# FPGA_Supply.net
KiCad netlist of a schematic drawn in Altium Designer
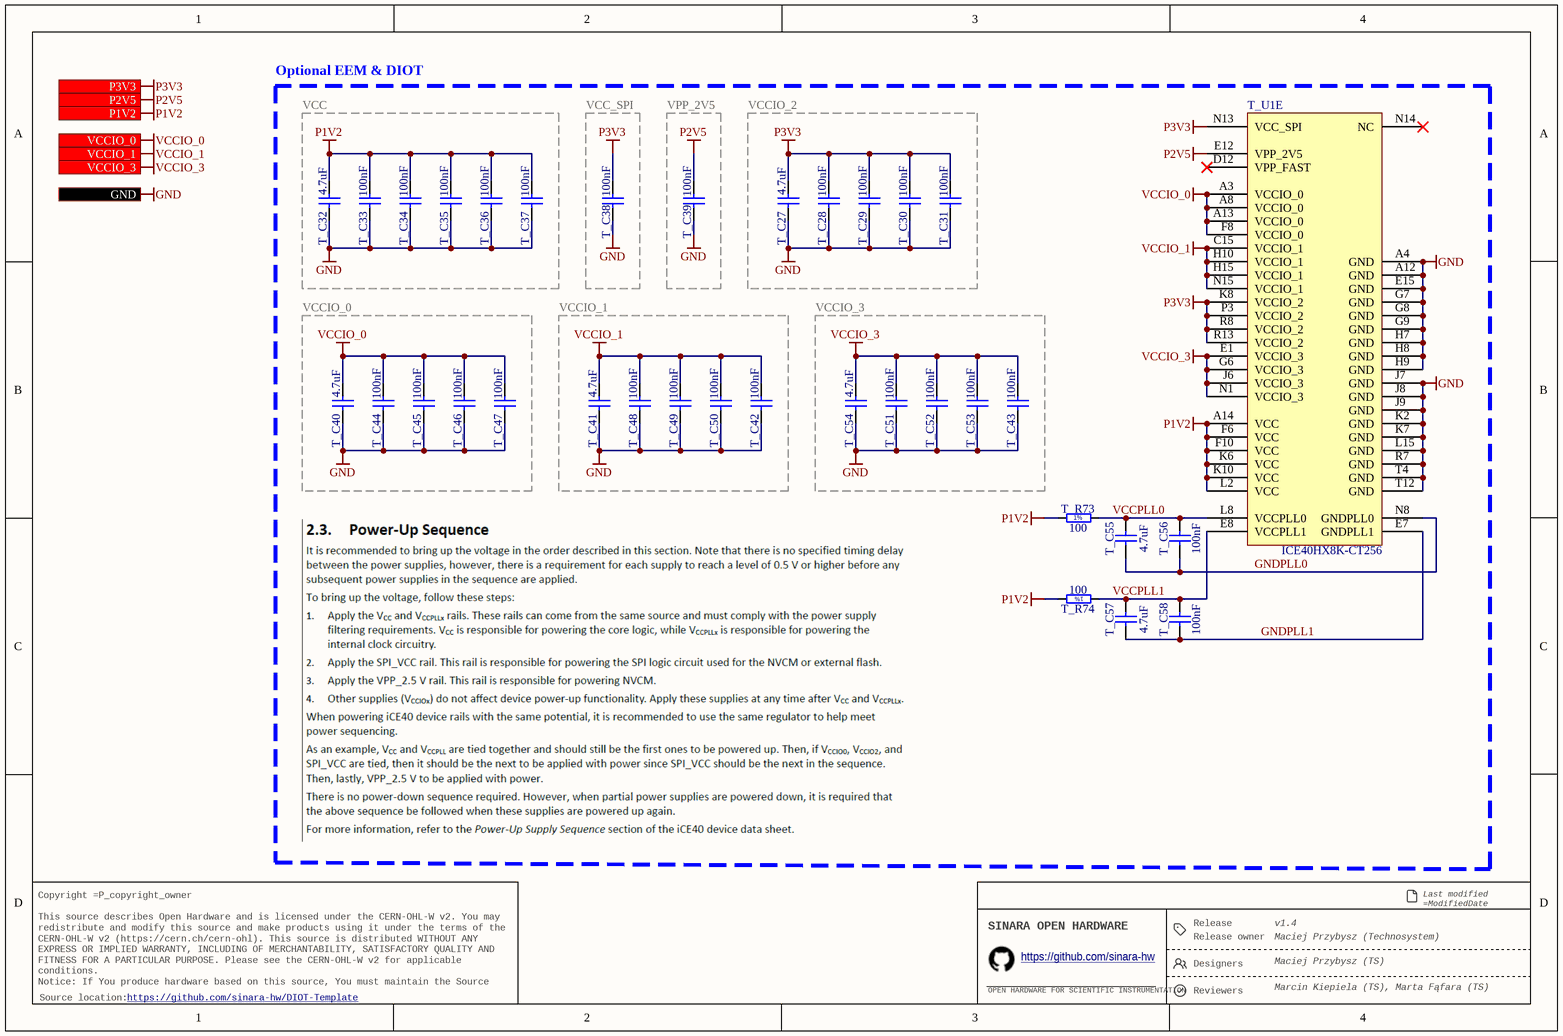
[diagram p0: FPGA_Supply.SchDoc]

(export (version "E")
  (design (tool "Eeschema 10.0.6"))
  (components
    (comp (ref "T_C27")
      (value "4.7uF")
      (footprint "CAPC2012X135N")
      (description "Non-polarised capacitor")
      (fields
        (field (name "PART NUMBER") "CC0805_4.7UF_16V_10%_X7R")
        (field (name "VOLTAGE") "16V")
        (field (name "AUTHOR") "CERN DEM JLC")
      )
      (libsource (lib "Capacitors") (part "Capacitor - non polarized"))
    )
    (comp (ref "T_C28")
      (value "100nF")
      (footprint "CAPC1005X55N")
      (description "Non-polarised capacitor")
      (fields
        (field (name "PART NUMBER") "CC0402_100NF_50V_10%_X7R")
        (field (name "VOLTAGE") "50V")
        (field (name "AUTHOR") "CERN DEM MR")
      )
      (libsource (lib "Capacitors") (part "Capacitor - non polarized"))
    )
    (comp (ref "T_C29")
      (value "100nF")
      (footprint "CAPC1005X55N")
      (description "Non-polarised capacitor")
      (fields
        (field (name "PART NUMBER") "CC0402_100NF_50V_10%_X7R")
        (field (name "VOLTAGE") "50V")
        (field (name "AUTHOR") "CERN DEM MR")
      )
      (libsource (lib "Capacitors") (part "Capacitor - non polarized"))
    )
    (comp (ref "T_C30")
      (value "100nF")
      (footprint "CAPC1005X55N")
      (description "Non-polarised capacitor")
      (fields
        (field (name "PART NUMBER") "CC0402_100NF_50V_10%_X7R")
        (field (name "VOLTAGE") "50V")
        (field (name "AUTHOR") "CERN DEM MR")
      )
      (libsource (lib "Capacitors") (part "Capacitor - non polarized"))
    )
    (comp (ref "T_C31")
      (value "100nF")
      (footprint "CAPC1005X55N")
      (description "Non-polarised capacitor")
      (fields
        (field (name "PART NUMBER") "CC0402_100NF_50V_10%_X7R")
        (field (name "VOLTAGE") "50V")
        (field (name "AUTHOR") "CERN DEM MR")
      )
      (libsource (lib "Capacitors") (part "Capacitor - non polarized"))
    )
    (comp (ref "T_C32")
      (value "4.7uF")
      (footprint "CAPC2012X135N")
      (description "Non-polarised capacitor")
      (fields
        (field (name "PART NUMBER") "CC0805_4.7UF_16V_10%_X7R")
        (field (name "VOLTAGE") "16V")
        (field (name "AUTHOR") "CERN DEM JLC")
      )
      (libsource (lib "Capacitors") (part "Capacitor - non polarized"))
    )
    (comp (ref "T_C33")
      (value "100nF")
      (footprint "CAPC1005X55N")
      (description "Non-polarised capacitor")
      (fields
        (field (name "PART NUMBER") "CC0402_100NF_50V_10%_X7R")
        (field (name "VOLTAGE") "50V")
        (field (name "AUTHOR") "CERN DEM MR")
      )
      (libsource (lib "Capacitors") (part "Capacitor - non polarized"))
    )
    (comp (ref "T_C34")
      (value "100nF")
      (footprint "CAPC1005X55N")
      (description "Non-polarised capacitor")
      (fields
        (field (name "PART NUMBER") "CC0402_100NF_50V_10%_X7R")
        (field (name "VOLTAGE") "50V")
        (field (name "AUTHOR") "CERN DEM MR")
      )
      (libsource (lib "Capacitors") (part "Capacitor - non polarized"))
    )
    (comp (ref "T_C35")
      (value "100nF")
      (footprint "CAPC1005X55N")
      (description "Non-polarised capacitor")
      (fields
        (field (name "PART NUMBER") "CC0402_100NF_50V_10%_X7R")
        (field (name "VOLTAGE") "50V")
        (field (name "AUTHOR") "CERN DEM MR")
      )
      (libsource (lib "Capacitors") (part "Capacitor - non polarized"))
    )
    (comp (ref "T_C36")
      (value "100nF")
      (footprint "CAPC1005X55N")
      (description "Non-polarised capacitor")
      (fields
        (field (name "PART NUMBER") "CC0402_100NF_50V_10%_X7R")
        (field (name "VOLTAGE") "50V")
        (field (name "AUTHOR") "CERN DEM MR")
      )
      (libsource (lib "Capacitors") (part "Capacitor - non polarized"))
    )
    (comp (ref "T_C37")
      (value "100nF")
      (footprint "CAPC1005X55N")
      (description "Non-polarised capacitor")
      (fields
        (field (name "PART NUMBER") "CC0402_100NF_50V_10%_X7R")
        (field (name "VOLTAGE") "50V")
        (field (name "AUTHOR") "CERN DEM MR")
      )
      (libsource (lib "Capacitors") (part "Capacitor - non polarized"))
    )
    (comp (ref "T_C38")
      (value "100nF")
      (footprint "CAPC1005X55N")
      (description "Non-polarised capacitor")
      (fields
        (field (name "PART NUMBER") "CC0402_100NF_50V_10%_X7R")
        (field (name "VOLTAGE") "50V")
        (field (name "AUTHOR") "CERN DEM MR")
      )
      (libsource (lib "Capacitors") (part "Capacitor - non polarized"))
    )
    (comp (ref "T_C39")
      (value "100nF")
      (footprint "CAPC1005X55N")
      (description "Non-polarised capacitor")
      (fields
        (field (name "PART NUMBER") "CC0402_100NF_50V_10%_X7R")
        (field (name "VOLTAGE") "50V")
        (field (name "AUTHOR") "CERN DEM MR")
      )
      (libsource (lib "Capacitors") (part "Capacitor - non polarized"))
    )
    (comp (ref "T_C40")
      (value "4.7uF")
      (footprint "CAPC2012X135N")
      (description "Non-polarised capacitor")
      (fields
        (field (name "PART NUMBER") "CC0805_4.7UF_16V_10%_X7R")
        (field (name "VOLTAGE") "16V")
        (field (name "AUTHOR") "CERN DEM JLC")
      )
      (libsource (lib "Capacitors") (part "Capacitor - non polarized"))
    )
    (comp (ref "T_C41")
      (value "4.7uF")
      (footprint "CAPC2012X135N")
      (description "Non-polarised capacitor")
      (fields
        (field (name "PART NUMBER") "CC0805_4.7UF_16V_10%_X7R")
        (field (name "VOLTAGE") "16V")
        (field (name "AUTHOR") "CERN DEM JLC")
      )
      (libsource (lib "Capacitors") (part "Capacitor - non polarized"))
    )
    (comp (ref "T_C42")
      (value "100nF")
      (footprint "CAPC1005X55N")
      (description "Non-polarised capacitor")
      (fields
        (field (name "PART NUMBER") "CC0402_100NF_50V_10%_X7R")
        (field (name "VOLTAGE") "50V")
        (field (name "AUTHOR") "CERN DEM MR")
      )
      (libsource (lib "Capacitors") (part "Capacitor - non polarized"))
    )
    (comp (ref "T_C43")
      (value "100nF")
      (footprint "CAPC1005X55N")
      (description "Non-polarised capacitor")
      (fields
        (field (name "PART NUMBER") "CC0402_100NF_50V_10%_X7R")
        (field (name "VOLTAGE") "50V")
        (field (name "AUTHOR") "CERN DEM MR")
      )
      (libsource (lib "Capacitors") (part "Capacitor - non polarized"))
    )
    (comp (ref "T_C44")
      (value "100nF")
      (footprint "CAPC1005X55N")
      (description "Non-polarised capacitor")
      (fields
        (field (name "PART NUMBER") "CC0402_100NF_50V_10%_X7R")
        (field (name "VOLTAGE") "50V")
        (field (name "AUTHOR") "CERN DEM MR")
      )
      (libsource (lib "Capacitors") (part "Capacitor - non polarized"))
    )
    (comp (ref "T_C45")
      (value "100nF")
      (footprint "CAPC1005X55N")
      (description "Non-polarised capacitor")
      (fields
        (field (name "PART NUMBER") "CC0402_100NF_50V_10%_X7R")
        (field (name "VOLTAGE") "50V")
        (field (name "AUTHOR") "CERN DEM MR")
      )
      (libsource (lib "Capacitors") (part "Capacitor - non polarized"))
    )
    (comp (ref "T_C46")
      (value "100nF")
      (footprint "CAPC1005X55N")
      (description "Non-polarised capacitor")
      (fields
        (field (name "PART NUMBER") "CC0402_100NF_50V_10%_X7R")
        (field (name "VOLTAGE") "50V")
        (field (name "AUTHOR") "CERN DEM MR")
      )
      (libsource (lib "Capacitors") (part "Capacitor - non polarized"))
    )
    (comp (ref "T_C47")
      (value "100nF")
      (footprint "CAPC1005X55N")
      (description "Non-polarised capacitor")
      (fields
        (field (name "PART NUMBER") "CC0402_100NF_50V_10%_X7R")
        (field (name "VOLTAGE") "50V")
        (field (name "AUTHOR") "CERN DEM MR")
      )
      (libsource (lib "Capacitors") (part "Capacitor - non polarized"))
    )
    (comp (ref "T_C48")
      (value "100nF")
      (footprint "CAPC1005X55N")
      (description "Non-polarised capacitor")
      (fields
        (field (name "PART NUMBER") "CC0402_100NF_50V_10%_X7R")
        (field (name "VOLTAGE") "50V")
        (field (name "AUTHOR") "CERN DEM MR")
      )
      (libsource (lib "Capacitors") (part "Capacitor - non polarized"))
    )
    (comp (ref "T_C49")
      (value "100nF")
      (footprint "CAPC1005X55N")
      (description "Non-polarised capacitor")
      (fields
        (field (name "PART NUMBER") "CC0402_100NF_50V_10%_X7R")
        (field (name "VOLTAGE") "50V")
        (field (name "AUTHOR") "CERN DEM MR")
      )
      (libsource (lib "Capacitors") (part "Capacitor - non polarized"))
    )
    (comp (ref "T_C50")
      (value "100nF")
      (footprint "CAPC1005X55N")
      (description "Non-polarised capacitor")
      (fields
        (field (name "PART NUMBER") "CC0402_100NF_50V_10%_X7R")
        (field (name "VOLTAGE") "50V")
        (field (name "AUTHOR") "CERN DEM MR")
      )
      (libsource (lib "Capacitors") (part "Capacitor - non polarized"))
    )
    (comp (ref "T_C51")
      (value "100nF")
      (footprint "CAPC1005X55N")
      (description "Non-polarised capacitor")
      (fields
        (field (name "PART NUMBER") "CC0402_100NF_50V_10%_X7R")
        (field (name "VOLTAGE") "50V")
        (field (name "AUTHOR") "CERN DEM MR")
      )
      (libsource (lib "Capacitors") (part "Capacitor - non polarized"))
    )
    (comp (ref "T_C52")
      (value "100nF")
      (footprint "CAPC1005X55N")
      (description "Non-polarised capacitor")
      (fields
        (field (name "PART NUMBER") "CC0402_100NF_50V_10%_X7R")
        (field (name "VOLTAGE") "50V")
        (field (name "AUTHOR") "CERN DEM MR")
      )
      (libsource (lib "Capacitors") (part "Capacitor - non polarized"))
    )
    (comp (ref "T_C53")
      (value "100nF")
      (footprint "CAPC1005X55N")
      (description "Non-polarised capacitor")
      (fields
        (field (name "PART NUMBER") "CC0402_100NF_50V_10%_X7R")
        (field (name "VOLTAGE") "50V")
        (field (name "AUTHOR") "CERN DEM MR")
      )
      (libsource (lib "Capacitors") (part "Capacitor - non polarized"))
    )
    (comp (ref "T_C54")
      (value "4.7uF")
      (footprint "CAPC2012X135N")
      (description "Non-polarised capacitor")
      (fields
        (field (name "PART NUMBER") "CC0805_4.7UF_16V_10%_X7R")
        (field (name "VOLTAGE") "16V")
        (field (name "AUTHOR") "CERN DEM JLC")
      )
      (libsource (lib "Capacitors") (part "Capacitor - non polarized"))
    )
    (comp (ref "T_C55")
      (value "4.7uF")
      (footprint "CAPC2012X135N")
      (description "Non-polarised capacitor")
      (fields
        (field (name "PART NUMBER") "CC0805_4.7UF_16V_10%_X7R")
        (field (name "VOLTAGE") "16V")
        (field (name "AUTHOR") "CERN DEM JLC")
      )
      (libsource (lib "Capacitors") (part "Capacitor - non polarized"))
    )
    (comp (ref "T_C56")
      (value "100nF")
      (footprint "CAPC1005X55N")
      (description "Non-polarised capacitor")
      (fields
        (field (name "PART NUMBER") "CC0402_100NF_50V_10%_X7R")
        (field (name "VOLTAGE") "50V")
        (field (name "AUTHOR") "CERN DEM MR")
      )
      (libsource (lib "Capacitors") (part "Capacitor - non polarized"))
    )
    (comp (ref "T_C57")
      (value "4.7uF")
      (footprint "CAPC2012X135N")
      (description "Non-polarised capacitor")
      (fields
        (field (name "PART NUMBER") "CC0805_4.7UF_16V_10%_X7R")
        (field (name "VOLTAGE") "16V")
        (field (name "AUTHOR") "CERN DEM JLC")
      )
      (libsource (lib "Capacitors") (part "Capacitor - non polarized"))
    )
    (comp (ref "T_C58")
      (value "100nF")
      (footprint "CAPC1005X55N")
      (description "Non-polarised capacitor")
      (fields
        (field (name "PART NUMBER") "CC0402_100NF_50V_10%_X7R")
        (field (name "VOLTAGE") "50V")
        (field (name "AUTHOR") "CERN DEM MR")
      )
      (libsource (lib "Capacitors") (part "Capacitor - non polarized"))
    )
    (comp (ref "T_R73")
      (value "100")
      (footprint "RESC1005X40N")
      (description "Resistor - 1%")
      (fields
        (field (name "PART NUMBER") "R0402_100R_1%_0.0625W_100PPM")
        (field (name "POWER") "0.0625W")
        (field (name "AUTHOR") "CERN DEM JLC")
      )
      (libsource (lib "Resistors") (part "Resistor - 1%"))
    )
    (comp (ref "T_R74")
      (value "100")
      (footprint "RESC1005X40N")
      (description "Resistor - 1%")
      (fields
        (field (name "PART NUMBER") "R0402_100R_1%_0.0625W_100PPM")
        (field (name "POWER") "0.0625W")
        (field (name "AUTHOR") "CERN DEM JLC")
      )
      (libsource (lib "Resistors") (part "Resistor - 1%"))
    )
    (comp (ref "T_U1")
      (value "ICE40HX8K-CT256")
      (footprint "LATC-caBGA-256")
      (fields (field (name "MANUFACTURER") "Lattice Semiconductor"))
      (libsource (lib "Altium Content Vault") (part "LATC-HX8K-caBGA-256"))
    )
  )
  (nets
    (net (code "1") (name "/GNDPLL0") (class "Default")
      (node (ref "T_C55") (pin "1") (pinfunction "1_1") (pintype "passive"))
      (node (ref "T_C56") (pin "1") (pinfunction "1_1") (pintype "passive"))
      (node (ref "T_U1") (pin "N8") (pinfunction "GNDPLL0_N8") (pintype "power_in"))
    )
    (net (code "2") (name "/GNDPLL1") (class "Default")
      (node (ref "T_C57") (pin "1") (pinfunction "1_1") (pintype "passive"))
      (node (ref "T_C58") (pin "1") (pinfunction "1_1") (pintype "passive"))
      (node (ref "T_U1") (pin "E7") (pinfunction "GNDPLL1_E7") (pintype "power_in"))
    )
    (net (code "3") (name "/VCCPLL0") (class "Default")
      (node (ref "T_C55") (pin "2") (pinfunction "2_2") (pintype "passive"))
      (node (ref "T_C56") (pin "2") (pinfunction "2_2") (pintype "passive"))
      (node (ref "T_R73") (pin "2") (pinfunction "2_2") (pintype "passive"))
      (node (ref "T_U1") (pin "L8") (pinfunction "VCCPLL0_L8") (pintype "power_in"))
    )
    (net (code "4") (name "/VCCPLL1") (class "Default")
      (node (ref "T_C57") (pin "2") (pinfunction "2_2") (pintype "passive"))
      (node (ref "T_C58") (pin "2") (pinfunction "2_2") (pintype "passive"))
      (node (ref "T_R74") (pin "1") (pinfunction "1_1") (pintype "passive"))
      (node (ref "T_U1") (pin "E8") (pinfunction "VCCPLL1_E8") (pintype "power_in"))
    )
    (net (code "5") (name "GND") (class "Default")
      (node (ref "T_C27") (pin "1") (pinfunction "1_1") (pintype "passive"))
      (node (ref "T_C28") (pin "1") (pinfunction "1_1") (pintype "passive"))
      (node (ref "T_C29") (pin "1") (pinfunction "1_1") (pintype "passive"))
      (node (ref "T_C30") (pin "1") (pinfunction "1_1") (pintype "passive"))
      (node (ref "T_C31") (pin "1") (pinfunction "1_1") (pintype "passive"))
      (node (ref "T_C32") (pin "1") (pinfunction "1_1") (pintype "passive"))
      (node (ref "T_C33") (pin "1") (pinfunction "1_1") (pintype "passive"))
      (node (ref "T_C34") (pin "1") (pinfunction "1_1") (pintype "passive"))
      (node (ref "T_C35") (pin "1") (pinfunction "1_1") (pintype "passive"))
      (node (ref "T_C36") (pin "1") (pinfunction "1_1") (pintype "passive"))
      (node (ref "T_C37") (pin "1") (pinfunction "1_1") (pintype "passive"))
      (node (ref "T_C38") (pin "1") (pinfunction "1_1") (pintype "passive"))
      (node (ref "T_C39") (pin "1") (pinfunction "1_1") (pintype "passive"))
      (node (ref "T_C40") (pin "1") (pinfunction "1_1") (pintype "passive"))
      (node (ref "T_C41") (pin "1") (pinfunction "1_1") (pintype "passive"))
      (node (ref "T_C42") (pin "1") (pinfunction "1_1") (pintype "passive"))
      (node (ref "T_C43") (pin "1") (pinfunction "1_1") (pintype "passive"))
      (node (ref "T_C44") (pin "1") (pinfunction "1_1") (pintype "passive"))
      (node (ref "T_C45") (pin "1") (pinfunction "1_1") (pintype "passive"))
      (node (ref "T_C46") (pin "1") (pinfunction "1_1") (pintype "passive"))
      (node (ref "T_C47") (pin "1") (pinfunction "1_1") (pintype "passive"))
      (node (ref "T_C48") (pin "1") (pinfunction "1_1") (pintype "passive"))
      (node (ref "T_C49") (pin "1") (pinfunction "1_1") (pintype "passive"))
      (node (ref "T_C50") (pin "1") (pinfunction "1_1") (pintype "passive"))
      (node (ref "T_C51") (pin "1") (pinfunction "1_1") (pintype "passive"))
      (node (ref "T_C52") (pin "1") (pinfunction "1_1") (pintype "passive"))
      (node (ref "T_C53") (pin "1") (pinfunction "1_1") (pintype "passive"))
      (node (ref "T_C54") (pin "1") (pinfunction "1_1") (pintype "passive"))
      (node (ref "T_U1") (pin "A12") (pinfunction "GND_A12") (pintype "power_in"))
      (node (ref "T_U1") (pin "A4") (pinfunction "GND_A4") (pintype "power_in"))
      (node (ref "T_U1") (pin "E15") (pinfunction "GND_E15") (pintype "power_in"))
      (node (ref "T_U1") (pin "G7") (pinfunction "GND_G7") (pintype "power_in"))
      (node (ref "T_U1") (pin "G8") (pinfunction "GND_G8") (pintype "power_in"))
      (node (ref "T_U1") (pin "G9") (pinfunction "GND_G9") (pintype "power_in"))
      (node (ref "T_U1") (pin "H7") (pinfunction "GND_H7") (pintype "power_in"))
      (node (ref "T_U1") (pin "H8") (pinfunction "GND_H8") (pintype "power_in"))
      (node (ref "T_U1") (pin "H9") (pinfunction "GND_H9") (pintype "power_in"))
      (node (ref "T_U1") (pin "J7") (pinfunction "GND_J7") (pintype "power_in"))
      (node (ref "T_U1") (pin "J8") (pinfunction "GND_J8") (pintype "power_in"))
      (node (ref "T_U1") (pin "J9") (pinfunction "GND_J9") (pintype "power_in"))
      (node (ref "T_U1") (pin "K2") (pinfunction "GND_K2") (pintype "power_in"))
      (node (ref "T_U1") (pin "K7") (pinfunction "GND_K7") (pintype "power_in"))
      (node (ref "T_U1") (pin "L15") (pinfunction "GND_L15") (pintype "power_in"))
      (node (ref "T_U1") (pin "R7") (pinfunction "GND_R7") (pintype "power_in"))
      (node (ref "T_U1") (pin "T12") (pinfunction "GND_T12") (pintype "power_in"))
      (node (ref "T_U1") (pin "T4") (pinfunction "GND_T4") (pintype "power_in"))
    )
    (net (code "6") (name "P1V2") (class "Default")
      (node (ref "T_C32") (pin "2") (pinfunction "2_2") (pintype "passive"))
      (node (ref "T_C33") (pin "2") (pinfunction "2_2") (pintype "passive"))
      (node (ref "T_C34") (pin "2") (pinfunction "2_2") (pintype "passive"))
      (node (ref "T_C35") (pin "2") (pinfunction "2_2") (pintype "passive"))
      (node (ref "T_C36") (pin "2") (pinfunction "2_2") (pintype "passive"))
      (node (ref "T_C37") (pin "2") (pinfunction "2_2") (pintype "passive"))
      (node (ref "T_R73") (pin "1") (pinfunction "1_1") (pintype "passive"))
      (node (ref "T_R74") (pin "2") (pinfunction "2_2") (pintype "passive"))
      (node (ref "T_U1") (pin "A14") (pinfunction "VCC_A14") (pintype "power_in"))
      (node (ref "T_U1") (pin "F10") (pinfunction "VCC_F10") (pintype "power_in"))
      (node (ref "T_U1") (pin "F6") (pinfunction "VCC_F6") (pintype "power_in"))
      (node (ref "T_U1") (pin "K10") (pinfunction "VCC_K10") (pintype "power_in"))
      (node (ref "T_U1") (pin "K6") (pinfunction "VCC_K6") (pintype "power_in"))
      (node (ref "T_U1") (pin "L2") (pinfunction "VCC_L2") (pintype "power_in"))
    )
    (net (code "7") (name "P2V5") (class "Default")
      (node (ref "T_C39") (pin "2") (pinfunction "2_2") (pintype "passive"))
      (node (ref "T_U1") (pin "E12") (pinfunction "VPP_2V5_E12") (pintype "power_in"))
    )
    (net (code "8") (name "P3V3") (class "Default")
      (node (ref "T_C27") (pin "2") (pinfunction "2_2") (pintype "passive"))
      (node (ref "T_C28") (pin "2") (pinfunction "2_2") (pintype "passive"))
      (node (ref "T_C29") (pin "2") (pinfunction "2_2") (pintype "passive"))
      (node (ref "T_C30") (pin "2") (pinfunction "2_2") (pintype "passive"))
      (node (ref "T_C31") (pin "2") (pinfunction "2_2") (pintype "passive"))
      (node (ref "T_C38") (pin "2") (pinfunction "2_2") (pintype "passive"))
      (node (ref "T_U1") (pin "K8") (pinfunction "VCCIO_2_K8") (pintype "power_in"))
      (node (ref "T_U1") (pin "N13") (pinfunction "VCC_SPI_N13") (pintype "power_in"))
      (node (ref "T_U1") (pin "P3") (pinfunction "VCCIO_2_P3") (pintype "power_in"))
      (node (ref "T_U1") (pin "R13") (pinfunction "VCCIO_2_R13") (pintype "power_in"))
      (node (ref "T_U1") (pin "R8") (pinfunction "VCCIO_2_R8") (pintype "power_in"))
    )
    (net (code "9") (name "VCCIO_0") (class "Default")
      (node (ref "T_C40") (pin "2") (pinfunction "2_2") (pintype "passive"))
      (node (ref "T_C44") (pin "2") (pinfunction "2_2") (pintype "passive"))
      (node (ref "T_C45") (pin "2") (pinfunction "2_2") (pintype "passive"))
      (node (ref "T_C46") (pin "2") (pinfunction "2_2") (pintype "passive"))
      (node (ref "T_C47") (pin "2") (pinfunction "2_2") (pintype "passive"))
      (node (ref "T_U1") (pin "A13") (pinfunction "VCCIO_0_A13") (pintype "power_in"))
      (node (ref "T_U1") (pin "A3") (pinfunction "VCCIO_0_A3") (pintype "power_in"))
      (node (ref "T_U1") (pin "A8") (pinfunction "VCCIO_0_A8") (pintype "power_in"))
      (node (ref "T_U1") (pin "F8") (pinfunction "VCCIO_0_F8") (pintype "power_in"))
    )
    (net (code "10") (name "VCCIO_1") (class "Default")
      (node (ref "T_C41") (pin "2") (pinfunction "2_2") (pintype "passive"))
      (node (ref "T_C42") (pin "2") (pinfunction "2_2") (pintype "passive"))
      (node (ref "T_C48") (pin "2") (pinfunction "2_2") (pintype "passive"))
      (node (ref "T_C49") (pin "2") (pinfunction "2_2") (pintype "passive"))
      (node (ref "T_C50") (pin "2") (pinfunction "2_2") (pintype "passive"))
      (node (ref "T_U1") (pin "C15") (pinfunction "VCCIO_1_C15") (pintype "power_in"))
      (node (ref "T_U1") (pin "H10") (pinfunction "VCCIO_1_H10") (pintype "power_in"))
      (node (ref "T_U1") (pin "H15") (pinfunction "VCCIO_1_H15") (pintype "power_in"))
      (node (ref "T_U1") (pin "N15") (pinfunction "VCCIO_1_N15") (pintype "power_in"))
    )
    (net (code "11") (name "VCCIO_3") (class "Default")
      (node (ref "T_C43") (pin "2") (pinfunction "2_2") (pintype "passive"))
      (node (ref "T_C51") (pin "2") (pinfunction "2_2") (pintype "passive"))
      (node (ref "T_C52") (pin "2") (pinfunction "2_2") (pintype "passive"))
      (node (ref "T_C53") (pin "2") (pinfunction "2_2") (pintype "passive"))
      (node (ref "T_C54") (pin "2") (pinfunction "2_2") (pintype "passive"))
      (node (ref "T_U1") (pin "E1") (pinfunction "VCCIO_3_E1") (pintype "power_in"))
      (node (ref "T_U1") (pin "G6") (pinfunction "VCCIO_3_G6") (pintype "power_in"))
      (node (ref "T_U1") (pin "J6") (pinfunction "VCCIO_3_J6") (pintype "power_in"))
      (node (ref "T_U1") (pin "N1") (pinfunction "VCCIO_3_N1") (pintype "power_in"))
    )
    (net (code "12") (name "unconnected-(T_U1E-NC-PadN14)") (class "Default")
      (node (ref "T_U1") (pin "N14") (pinfunction "NC_N14") (pintype "passive+no_connect"))
    )
    (net (code "13") (name "unconnected-(T_U1E-VPP_FAST-PadD12)") (class "Default")
      (node (ref "T_U1") (pin "D12") (pinfunction "VPP_FAST_D12") (pintype "power_in+no_connect"))
    )
  )
)
